# 3_waffling60-MX_mcu.net
KiCad netlist of a schematic drawn in Altium Designer
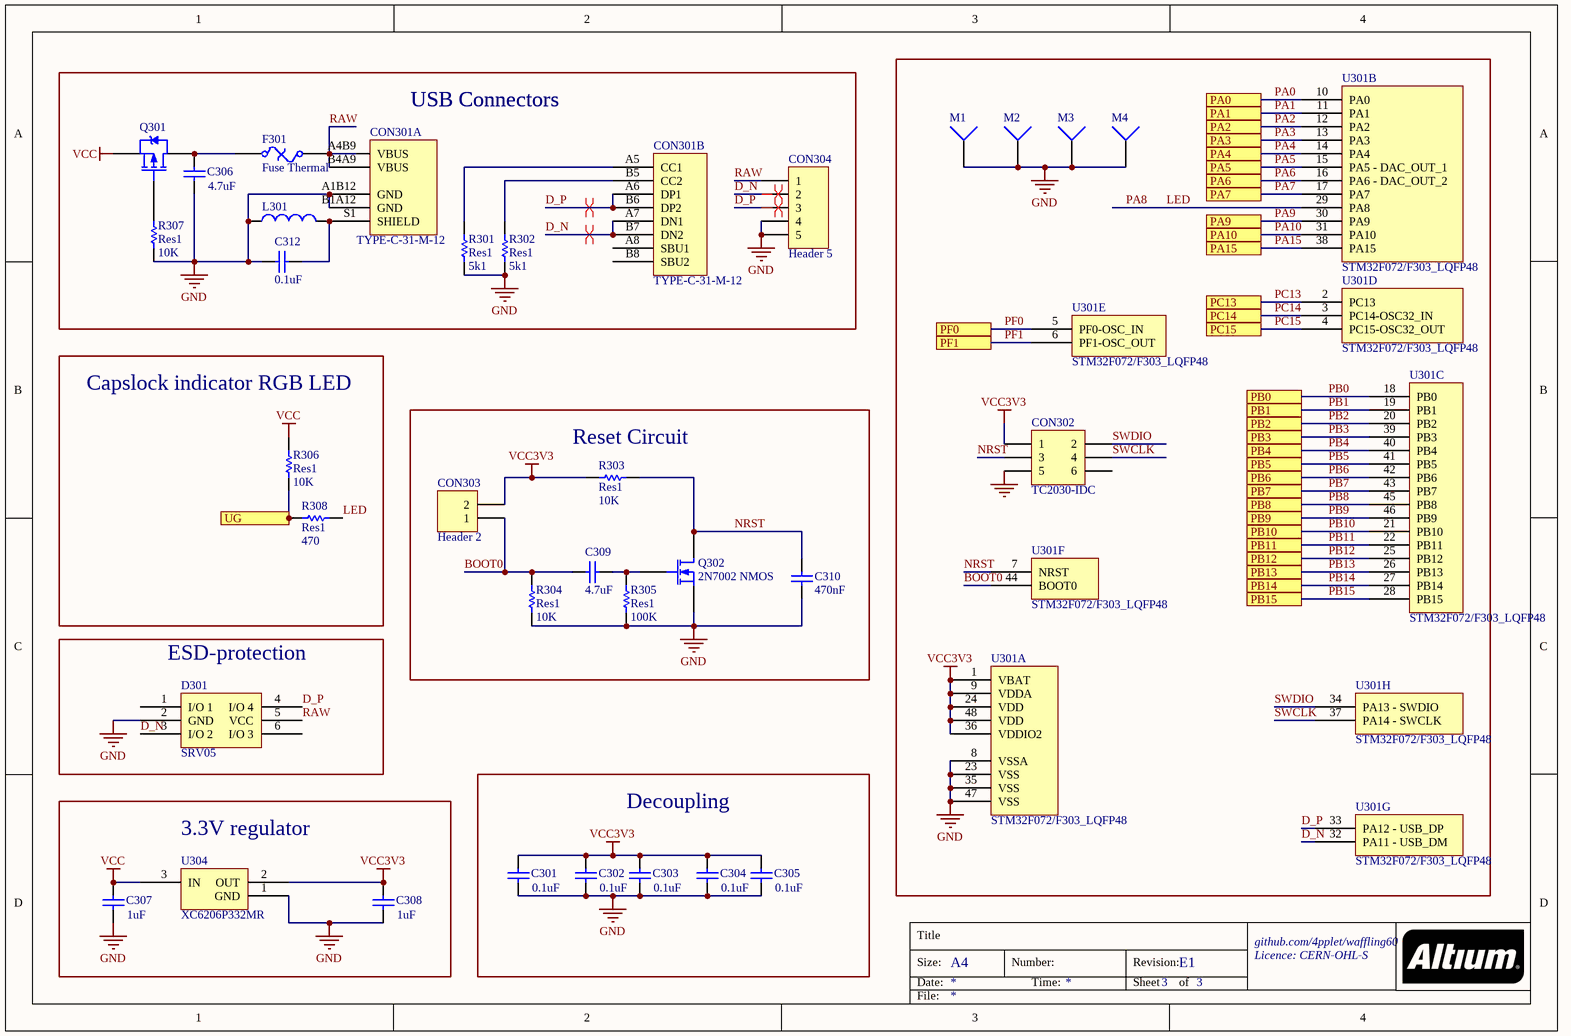
[diagram p0: 3_waffling60-MX_mcu.SchDoc]

(export (version "E")
  (design (tool "Eeschema 10.0.6"))
  (components
    (comp (ref "C301")
      (value "0.1uF")
      (footprint "C0603[1608]")
      (description "Capacitor")
      (fields (field (name "LCSC PART #") "C14663") (field (name "MRF.PART") "CC0603KRX7R9BB104"))
      (libsource (lib "Miscellaneous Devices") (part "Cap"))
    )
    (comp (ref "C302")
      (value "0.1uF")
      (footprint "C0603[1608]")
      (description "Capacitor")
      (fields (field (name "LCSC PART #") "C14663") (field (name "MRF.PART") "CC0603KRX7R9BB104"))
      (libsource (lib "Miscellaneous Devices") (part "Cap"))
    )
    (comp (ref "C303")
      (value "0.1uF")
      (footprint "C0603[1608]")
      (description "Capacitor")
      (fields (field (name "LCSC PART #") "C14663") (field (name "MRF.PART") "CC0603KRX7R9BB104"))
      (libsource (lib "Miscellaneous Devices") (part "Cap"))
    )
    (comp (ref "C304")
      (value "0.1uF")
      (footprint "C0603[1608]")
      (description "Capacitor")
      (fields (field (name "LCSC PART #") "C14663") (field (name "MRF.PART") "CC0603KRX7R9BB104"))
      (libsource (lib "Miscellaneous Devices") (part "Cap"))
    )
    (comp (ref "C305")
      (value "0.1uF")
      (footprint "C0603[1608]")
      (description "Capacitor")
      (fields (field (name "LCSC PART #") "C14663") (field (name "MRF.PART") "CC0603KRX7R9BB104"))
      (libsource (lib "Miscellaneous Devices") (part "Cap"))
    )
    (comp (ref "C306")
      (value "4.7uF")
      (footprint "C0603[1608]")
      (description "Capacitor")
      (fields (field (name "LCSC PART #") "C19666") (field (name "MRF.PART") "CL10A475KO8NNNC"))
      (libsource (lib "Miscellaneous Devices") (part "Cap"))
    )
    (comp (ref "C307")
      (value "1uF")
      (footprint "C0603[1608]")
      (description "Capacitor")
      (fields (field (name "LCSC PART #") "C15849") (field (name "MRF.PART") "CL10A105KB8NNNC"))
      (libsource (lib "Miscellaneous Devices") (part "Cap"))
    )
    (comp (ref "C308")
      (value "1uF")
      (footprint "C0603[1608]")
      (description "Capacitor")
      (fields (field (name "LCSC PART #") "C15849") (field (name "MRF.PART") "CL10A105KB8NNNC"))
      (libsource (lib "Miscellaneous Devices") (part "Cap"))
    )
    (comp (ref "C309")
      (value "4.7uF")
      (footprint "C0603[1608]")
      (description "Capacitor")
      (fields (field (name "LCSC PART #") "C19666") (field (name "MRF.PART") "CL10A475KO8NNNC"))
      (libsource (lib "Miscellaneous Devices") (part "Cap"))
    )
    (comp (ref "C310")
      (value "470nF")
      (footprint "C0603[1608]")
      (description "Capacitor")
      (fields (field (name "LCSC PART #") "C1623") (field (name "MRF.PART") "CL10B474KA8NNNC"))
      (libsource (lib "Miscellaneous Devices") (part "Cap"))
    )
    (comp (ref "C312")
      (value "0.1uF")
      (footprint "C0603[1608]")
      (description "Capacitor")
      (fields (field (name "LCSC PART #") "C14663") (field (name "MRF.PART") "CC0603KRX7R9BB104"))
      (libsource (lib "Miscellaneous Devices") (part "Cap"))
    )
    (comp (ref "CON301")
      (value "TYPE-C-31-M-12")
      (footprint "TYPE-C-31-M-12")
      (fields (field (name "LCSC PART #") "C165948"))
      (libsource (lib "Schlib1") (part "TYPE-C-31-M-12"))
    )
    (comp (ref "CON302")
      (value "TC2030-IDC")
      (footprint "TC2030-IDC-NL")
      (description "Header, 3-Pin, Dual row")
      (libsource (lib "Miscellaneous Connectors") (part "Header 3X2"))
    )
    (comp (ref "CON303")
      (value "Header 2")
      (footprint "HDR1X2")
      (description "Header, 2-Pin")
      (libsource (lib "Miscellaneous Connectors") (part "Header 2"))
    )
    (comp (ref "CON304")
      (value "Header 5")
      (footprint "Molex 781710004")
      (description "JST for USB daughter board")
      (fields (field (name "LCSC PART #") "C2840019") (field (name "MRF.PART") "M1201RS-04-BK"))
      (libsource (lib "Miscellaneous Connectors") (part "Header 5"))
    )
    (comp (ref "D301")
      (value "SRV05")
      (footprint "SOT-23-6")
      (fields (field (name "LCSC PART #") "C85364") (field (name "MRF.PART") "SRV05-4-P-T7"))
      (libsource (lib "Keebs") (part "SRV05"))
    )
    (comp (ref "F301")
      (value "Fuse Thermal")
      (footprint "C1206[3216]")
      (description "Thermal Fuse")
      (fields (field (name "LCSC PART #") "C135338") (field (name "MRF.PART") "ASMD1206-050"))
      (libsource (lib "Miscellaneous Devices") (part "Fuse Thermal"))
    )
    (comp (ref "L301")
      (value "Inductor")
      (footprint "L0805")
      (fields (field (name "LCSC PART #") "C1015") (field (name "MRF.PART") "GZ2012D101TF"))
      (libsource (lib "Simulation Generic Components") (part "Inductor"))
    )
    (comp (ref "M1")
      (value "Socket")
      (footprint "mounting_hole")
      (libsource (lib "Miscellaneous Connectors") (part "Socket"))
    )
    (comp (ref "M2")
      (value "Socket")
      (footprint "mounting_hole")
      (libsource (lib "Miscellaneous Connectors") (part "Socket"))
    )
    (comp (ref "M3")
      (value "Socket")
      (footprint "mounting_hole")
      (libsource (lib "Miscellaneous Connectors") (part "Socket"))
    )
    (comp (ref "M4")
      (value "Socket")
      (footprint "mounting_hole")
      (libsource (lib "Miscellaneous Connectors") (part "Socket"))
    )
    (comp (ref "Q301")
      (value "PMOS-2")
      (footprint "SOT-23-3")
      (description "P-Channel Power MOSFET")
      (fields (field (name "LCSC PART #") "C10487") (field (name "MRF.PART") "SI2301CDS-T1-GE3"))
      (libsource (lib "Miscellaneous Devices") (part "PMOS-2"))
    )
    (comp (ref "Q302")
      (value "2N7002 NMOS")
      (footprint "SOT-23-3")
      (description "N-Channel MOSFET")
      (fields (field (name "LCSC PART #") "C8545") (field (name "MRF.PART") "2N7002"))
      (libsource (lib "Miscellaneous Devices") (part "MOSFET-N"))
    )
    (comp (ref "R301")
      (value "Res1")
      (footprint "R0603[1608]")
      (description "Resistor")
      (fields
        (field (name "ALTIUM_VALUE") "5k1")
        (field (name "LCSC PART #") "C23186")
        (field (name "MRF.PART") "0603WAF5101T5E")
      )
      (libsource (lib "Miscellaneous Devices") (part "Res1"))
    )
    (comp (ref "R302")
      (value "Res1")
      (footprint "R0603[1608]")
      (description "Resistor")
      (fields
        (field (name "ALTIUM_VALUE") "5k1")
        (field (name "LCSC PART #") "C23186")
        (field (name "MRF.PART") "0603WAF5101T5E")
      )
      (libsource (lib "Miscellaneous Devices") (part "Res1"))
    )
    (comp (ref "R303")
      (value "Res1")
      (footprint "R0603[1608]")
      (description "Resistor")
      (fields
        (field (name "ALTIUM_VALUE") "10K")
        (field (name "LCSC PART #") "C25804")
        (field (name "MRF.PART") "0603WAF1002T5E")
      )
      (libsource (lib "Miscellaneous Devices") (part "Res1"))
    )
    (comp (ref "R304")
      (value "Res1")
      (footprint "R0603[1608]")
      (description "Resistor")
      (fields
        (field (name "ALTIUM_VALUE") "10K")
        (field (name "LCSC PART #") "C25804")
        (field (name "MRF.PART") "0603WAF1002T5E")
      )
      (libsource (lib "Miscellaneous Devices") (part "Res1"))
    )
    (comp (ref "R305")
      (value "Res1")
      (footprint "R0603[1608]")
      (description "Resistor")
      (fields
        (field (name "ALTIUM_VALUE") "100K")
        (field (name "LCSC PART #") "C25803")
        (field (name "MRF.PART") "0603WAF1003T5E")
      )
      (libsource (lib "Miscellaneous Devices") (part "Res1"))
    )
    (comp (ref "R306")
      (value "Res1")
      (footprint "R0603[1608]")
      (description "Resistor")
      (fields
        (field (name "ALTIUM_VALUE") "10K")
        (field (name "LCSC PART #") "C25804")
        (field (name "MRF.PART") "0603WAF1002T5E")
      )
      (libsource (lib "Miscellaneous Devices") (part "Res1"))
    )
    (comp (ref "R307")
      (value "Res1")
      (footprint "R0603[1608]")
      (description "Resistor")
      (fields
        (field (name "ALTIUM_VALUE") "10K")
        (field (name "LCSC PART #") "C25804")
        (field (name "MRF.PART") "0603WAF1002T5E")
      )
      (libsource (lib "Miscellaneous Devices") (part "Res1"))
    )
    (comp (ref "R308")
      (value "Res1")
      (footprint "R0603[1608]")
      (description "Resistor")
      (fields
        (field (name "ALTIUM_VALUE") "470")
        (field (name "LCSC PART #") "C23179")
        (field (name "MRF.PART") "0603WAF4700T5E")
      )
      (libsource (lib "Miscellaneous Devices") (part "Res1"))
    )
    (comp (ref "U301")
      (value "STM32F072/F303_LQFP48")
      (footprint "STM32 - COMBO 7X7MM")
      (fields (field (name "LCSC PART #") "C915660") (field (name "MRF.PART") "APM32F072CBT6"))
      (libsource (lib "") (part "STM32F072/F303_LQFP48_1"))
    )
    (comp (ref "U304")
      (value "XC6206P332MR")
      (footprint "SOT-23-3")
      (fields (field (name "LCSC PART #") "C5446"))
      (libsource (lib "Keebs") (part "SOT23 LDO"))
    )
  )
  (nets
    (net (code "1") (name "/BOOT0") (class "Default")
      (node (ref "C309") (pin "1") (pinfunction "1_1") (pintype "passive"))
      (node (ref "CON303") (pin "1") (pinfunction "1_1") (pintype "passive"))
      (node (ref "R304") (pin "1") (pinfunction "1_1") (pintype "passive"))
      (node (ref "U301") (pin "44") (pinfunction "BOOT0_44") (pintype "passive"))
    )
    (net (code "2") (name "/D_N") (class "Default")
      (node (ref "CON301") (pin "A7") (pinfunction "DN1_A7") (pintype "passive"))
      (node (ref "CON301") (pin "B7") (pinfunction "DN2_B7") (pintype "passive"))
      (node (ref "CON304") (pin "2") (pinfunction "2_2") (pintype "passive"))
      (node (ref "D301") (pin "3") (pinfunction "I/O_2_3") (pintype "passive"))
      (node (ref "U301") (pin "32") (pinfunction "PA11_-_USB_DM_32") (pintype "passive"))
    )
    (net (code "3") (name "/D_P") (class "Default")
      (node (ref "CON301") (pin "A6") (pinfunction "DP1_A6") (pintype "passive"))
      (node (ref "CON301") (pin "B6") (pinfunction "DP2_B6") (pintype "passive"))
      (node (ref "CON304") (pin "3") (pinfunction "3_3") (pintype "passive"))
      (node (ref "D301") (pin "4") (pinfunction "I/O_4_4") (pintype "passive"))
      (node (ref "U301") (pin "33") (pinfunction "PA12_-_USB_DP_33") (pintype "passive"))
    )
    (net (code "4") (name "/LED") (class "Default")
      (node (ref "R308") (pin "2") (pinfunction "2_2") (pintype "passive"))
      (node (ref "U301") (pin "29") (pinfunction "PA8_29") (pintype "passive"))
    )
    (net (code "5") (name "/NRST") (class "Default")
      (node (ref "C310") (pin "1") (pinfunction "1_1") (pintype "passive"))
      (node (ref "CON302") (pin "3") (pinfunction "3_3") (pintype "passive"))
      (node (ref "Q302") (pin "3") (pinfunction "D_3") (pintype "passive"))
      (node (ref "R303") (pin "2") (pinfunction "2_2") (pintype "passive"))
      (node (ref "U301") (pin "7") (pinfunction "NRST_7") (pintype "passive"))
    )
    (net (code "6") (name "/PA0") (class "Default")
      (node (ref "U301") (pin "10") (pinfunction "PA0_10") (pintype "passive"))
    )
    (net (code "7") (name "/PA1") (class "Default")
      (node (ref "U301") (pin "11") (pinfunction "PA1_11") (pintype "passive"))
    )
    (net (code "8") (name "/PA2") (class "Default")
      (node (ref "U301") (pin "12") (pinfunction "PA2_12") (pintype "passive"))
    )
    (net (code "9") (name "/PA3") (class "Default")
      (node (ref "U301") (pin "13") (pinfunction "PA3_13") (pintype "passive"))
    )
    (net (code "10") (name "/PA4") (class "Default")
      (node (ref "U301") (pin "14") (pinfunction "PA4_14") (pintype "passive"))
    )
    (net (code "11") (name "/PA5") (class "Default")
      (node (ref "U301") (pin "15") (pinfunction "PA5_-_DAC_OUT_1_15") (pintype "passive"))
    )
    (net (code "12") (name "/PA6") (class "Default")
      (node (ref "U301") (pin "16") (pinfunction "PA6_-_DAC_OUT_2_16") (pintype "passive"))
    )
    (net (code "13") (name "/PA7") (class "Default")
      (node (ref "U301") (pin "17") (pinfunction "PA7_17") (pintype "passive"))
    )
    (net (code "14") (name "/PA9") (class "Default")
      (node (ref "U301") (pin "30") (pinfunction "PA9_30") (pintype "passive"))
    )
    (net (code "15") (name "/PA10") (class "Default")
      (node (ref "U301") (pin "31") (pinfunction "PA10_31") (pintype "passive"))
    )
    (net (code "16") (name "/PA15") (class "Default")
      (node (ref "U301") (pin "38") (pinfunction "PA15_38") (pintype "passive"))
    )
    (net (code "17") (name "/PB0") (class "Default")
      (node (ref "U301") (pin "18") (pinfunction "PB0_18") (pintype "passive"))
    )
    (net (code "18") (name "/PB1") (class "Default")
      (node (ref "U301") (pin "19") (pinfunction "PB1_19") (pintype "passive"))
    )
    (net (code "19") (name "/PB2") (class "Default")
      (node (ref "U301") (pin "20") (pinfunction "PB2_20") (pintype "passive"))
    )
    (net (code "20") (name "/PB3") (class "Default")
      (node (ref "U301") (pin "39") (pinfunction "PB3_39") (pintype "passive"))
    )
    (net (code "21") (name "/PB4") (class "Default")
      (node (ref "U301") (pin "40") (pinfunction "PB4_40") (pintype "passive"))
    )
    (net (code "22") (name "/PB5") (class "Default")
      (node (ref "U301") (pin "41") (pinfunction "PB5_41") (pintype "passive"))
    )
    (net (code "23") (name "/PB6") (class "Default")
      (node (ref "U301") (pin "42") (pinfunction "PB6_42") (pintype "passive"))
    )
    (net (code "24") (name "/PB7") (class "Default")
      (node (ref "U301") (pin "43") (pinfunction "PB7_43") (pintype "passive"))
    )
    (net (code "25") (name "/PB8") (class "Default")
      (node (ref "U301") (pin "45") (pinfunction "PB8_45") (pintype "passive"))
    )
    (net (code "26") (name "/PB9") (class "Default")
      (node (ref "U301") (pin "46") (pinfunction "PB9_46") (pintype "passive"))
    )
    (net (code "27") (name "/PB10") (class "Default")
      (node (ref "U301") (pin "21") (pinfunction "PB10_21") (pintype "passive"))
    )
    (net (code "28") (name "/PB11") (class "Default")
      (node (ref "U301") (pin "22") (pinfunction "PB11_22") (pintype "passive"))
    )
    (net (code "29") (name "/PB12") (class "Default")
      (node (ref "U301") (pin "25") (pinfunction "PB12_25") (pintype "passive"))
    )
    (net (code "30") (name "/PB13") (class "Default")
      (node (ref "U301") (pin "26") (pinfunction "PB13_26") (pintype "passive"))
    )
    (net (code "31") (name "/PB14") (class "Default")
      (node (ref "U301") (pin "27") (pinfunction "PB14_27") (pintype "passive"))
    )
    (net (code "32") (name "/PB15") (class "Default")
      (node (ref "U301") (pin "28") (pinfunction "PB15_28") (pintype "passive"))
    )
    (net (code "33") (name "/PC13") (class "Default")
      (node (ref "U301") (pin "2") (pinfunction "PC13_2") (pintype "passive"))
    )
    (net (code "34") (name "/PC14") (class "Default")
      (node (ref "U301") (pin "3") (pinfunction "PC14-OSC32_IN_3") (pintype "passive"))
    )
    (net (code "35") (name "/PC15") (class "Default")
      (node (ref "U301") (pin "4") (pinfunction "PC15-OSC32_OUT_4") (pintype "passive"))
    )
    (net (code "36") (name "/PF0") (class "Default")
      (node (ref "U301") (pin "5") (pinfunction "PF0-OSC_IN_5") (pintype "passive"))
    )
    (net (code "37") (name "/PF1") (class "Default")
      (node (ref "U301") (pin "6") (pinfunction "PF1-OSC_OUT_6") (pintype "passive"))
    )
    (net (code "38") (name "/RAW") (class "Default")
      (node (ref "CON301") (pin "A4B9") (pinfunction "VBUS_A4B9") (pintype "passive"))
      (node (ref "CON301") (pin "B4A9") (pinfunction "VBUS_B4A9") (pintype "passive"))
      (node (ref "CON304") (pin "1") (pinfunction "1_1") (pintype "passive"))
      (node (ref "D301") (pin "5") (pinfunction "VCC_5") (pintype "passive"))
      (node (ref "F301") (pin "2") (pinfunction "2_2") (pintype "passive"))
    )
    (net (code "39") (name "/SWCLK") (class "Default")
      (node (ref "CON302") (pin "4") (pinfunction "4_4") (pintype "passive"))
      (node (ref "U301") (pin "37") (pinfunction "PA14_-_SWCLK_37") (pintype "passive"))
    )
    (net (code "40") (name "/SWDIO") (class "Default")
      (node (ref "CON302") (pin "2") (pinfunction "2_2") (pintype "passive"))
      (node (ref "U301") (pin "34") (pinfunction "PA13_-_SWDIO_34") (pintype "passive"))
    )
    (net (code "41") (name "/UG") (class "Default")
      (node (ref "R306") (pin "2") (pinfunction "2_2") (pintype "passive"))
      (node (ref "R308") (pin "1") (pinfunction "1_1") (pintype "passive"))
    )
    (net (code "42") (name "GND") (class "Default")
      (node (ref "C301") (pin "1") (pinfunction "1_1") (pintype "passive"))
      (node (ref "C302") (pin "1") (pinfunction "1_1") (pintype "passive"))
      (node (ref "C303") (pin "1") (pinfunction "1_1") (pintype "passive"))
      (node (ref "C304") (pin "1") (pinfunction "1_1") (pintype "passive"))
      (node (ref "C305") (pin "1") (pinfunction "1_1") (pintype "passive"))
      (node (ref "C306") (pin "1") (pinfunction "1_1") (pintype "passive"))
      (node (ref "C307") (pin "1") (pinfunction "1_1") (pintype "passive"))
      (node (ref "C308") (pin "1") (pinfunction "1_1") (pintype "passive"))
      (node (ref "C310") (pin "2") (pinfunction "2_2") (pintype "passive"))
      (node (ref "C312") (pin "1") (pinfunction "1_1") (pintype "passive"))
      (node (ref "CON301") (pin "A1B12") (pinfunction "GND_A1B12") (pintype "passive"))
      (node (ref "CON301") (pin "B1A12") (pinfunction "GND_B1A12") (pintype "passive"))
      (node (ref "CON302") (pin "5") (pinfunction "5_5") (pintype "passive"))
      (node (ref "CON304") (pin "4") (pinfunction "4_4") (pintype "passive"))
      (node (ref "CON304") (pin "5") (pinfunction "5_5") (pintype "passive"))
      (node (ref "D301") (pin "2") (pinfunction "GND_2") (pintype "passive"))
      (node (ref "L301") (pin "1") (pinfunction "1_1") (pintype "passive"))
      (node (ref "M1") (pin "1") (pinfunction "1_1") (pintype "passive"))
      (node (ref "M2") (pin "1") (pinfunction "1_1") (pintype "passive"))
      (node (ref "M3") (pin "1") (pinfunction "1_1") (pintype "passive"))
      (node (ref "M4") (pin "1") (pinfunction "1_1") (pintype "passive"))
      (node (ref "Q302") (pin "2") (pinfunction "S_2") (pintype "passive"))
      (node (ref "R301") (pin "2") (pinfunction "2_2") (pintype "passive"))
      (node (ref "R302") (pin "2") (pinfunction "2_2") (pintype "passive"))
      (node (ref "R304") (pin "2") (pinfunction "2_2") (pintype "passive"))
      (node (ref "R305") (pin "2") (pinfunction "2_2") (pintype "passive"))
      (node (ref "R307") (pin "2") (pinfunction "2_2") (pintype "passive"))
      (node (ref "U301") (pin "23") (pinfunction "VSS_23") (pintype "passive"))
      (node (ref "U301") (pin "35") (pinfunction "VSS_35") (pintype "passive"))
      (node (ref "U301") (pin "47") (pinfunction "VSS_47") (pintype "passive"))
      (node (ref "U301") (pin "8") (pinfunction "VSSA_8") (pintype "passive"))
      (node (ref "U304") (pin "1") (pinfunction "GND_1") (pintype "passive"))
    )
    (net (code "43") (name "Net-(CON301A-SHIELD)") (class "Default")
      (node (ref "C312") (pin "2") (pinfunction "2_2") (pintype "passive"))
      (node (ref "CON301") (pin "S1") (pinfunction "SHIELD_S1") (pintype "passive"))
      (node (ref "L301") (pin "2") (pinfunction "2_2") (pintype "passive"))
    )
    (net (code "44") (name "Net-(CON301B-CC1)") (class "Default")
      (node (ref "CON301") (pin "A5") (pinfunction "CC1_A5") (pintype "passive"))
      (node (ref "R301") (pin "1") (pinfunction "1_1") (pintype "passive"))
    )
    (net (code "45") (name "Net-(CON301B-CC2)") (class "Default")
      (node (ref "CON301") (pin "B5") (pinfunction "CC2_B5") (pintype "passive"))
      (node (ref "R302") (pin "1") (pinfunction "1_1") (pintype "passive"))
    )
    (net (code "46") (name "Net-(Q301-D)") (class "Default")
      (node (ref "C306") (pin "2") (pinfunction "2_2") (pintype "passive"))
      (node (ref "F301") (pin "1") (pinfunction "1_1") (pintype "passive"))
      (node (ref "Q301") (pin "3") (pinfunction "D_3") (pintype "passive"))
    )
    (net (code "47") (name "Net-(Q301-G)") (class "Default")
      (node (ref "Q301") (pin "1") (pinfunction "G_1") (pintype "passive"))
      (node (ref "R307") (pin "1") (pinfunction "1_1") (pintype "passive"))
    )
    (net (code "48") (name "Net-(Q302-G)") (class "Default")
      (node (ref "C309") (pin "2") (pinfunction "2_2") (pintype "passive"))
      (node (ref "Q302") (pin "1") (pinfunction "G_1") (pintype "passive"))
      (node (ref "R305") (pin "1") (pinfunction "1_1") (pintype "passive"))
    )
    (net (code "49") (name "VCC") (class "Default")
      (node (ref "C307") (pin "2") (pinfunction "2_2") (pintype "passive"))
      (node (ref "Q301") (pin "2") (pinfunction "S_2") (pintype "passive"))
      (node (ref "R306") (pin "1") (pinfunction "1_1") (pintype "passive"))
      (node (ref "U304") (pin "3") (pinfunction "IN_3") (pintype "passive"))
    )
    (net (code "50") (name "VCC3V3") (class "Default")
      (node (ref "C301") (pin "2") (pinfunction "2_2") (pintype "passive"))
      (node (ref "C302") (pin "2") (pinfunction "2_2") (pintype "passive"))
      (node (ref "C303") (pin "2") (pinfunction "2_2") (pintype "passive"))
      (node (ref "C304") (pin "2") (pinfunction "2_2") (pintype "passive"))
      (node (ref "C305") (pin "2") (pinfunction "2_2") (pintype "passive"))
      (node (ref "C308") (pin "2") (pinfunction "2_2") (pintype "passive"))
      (node (ref "CON302") (pin "1") (pinfunction "1_1") (pintype "passive"))
      (node (ref "CON303") (pin "2") (pinfunction "2_2") (pintype "passive"))
      (node (ref "R303") (pin "1") (pinfunction "1_1") (pintype "passive"))
      (node (ref "U301") (pin "1") (pinfunction "VBAT_1") (pintype "passive"))
      (node (ref "U301") (pin "24") (pinfunction "VDD_24") (pintype "passive"))
      (node (ref "U301") (pin "36") (pinfunction "VDDIO2_36") (pintype "passive"))
      (node (ref "U301") (pin "48") (pinfunction "VDD_48") (pintype "passive"))
      (node (ref "U301") (pin "9") (pinfunction "VDDA_9") (pintype "passive"))
      (node (ref "U304") (pin "2") (pinfunction "OUT_2") (pintype "passive"))
    )
    (net (code "51") (name "unconnected-(CON301B-SBU1-PadA8)") (class "Default")
      (node (ref "CON301") (pin "A8") (pinfunction "SBU1_A8") (pintype "passive"))
    )
    (net (code "52") (name "unconnected-(CON301B-SBU2-PadB8)") (class "Default")
      (node (ref "CON301") (pin "B8") (pinfunction "SBU2_B8") (pintype "passive"))
    )
    (net (code "53") (name "unconnected-(CON302-Pad6)") (class "Default")
      (node (ref "CON302") (pin "6") (pinfunction "6_6") (pintype "passive"))
    )
    (net (code "54") (name "unconnected-(D301-I{slash}O_1-Pad1)") (class "Default")
      (node (ref "D301") (pin "1") (pinfunction "I/O_1_1") (pintype "passive"))
    )
    (net (code "55") (name "unconnected-(D301-I{slash}O_3-Pad6)") (class "Default")
      (node (ref "D301") (pin "6") (pinfunction "I/O_3_6") (pintype "passive"))
    )
  )
)
